# mainboard_3.net
KiCad netlist of a schematic drawn in EAGLE
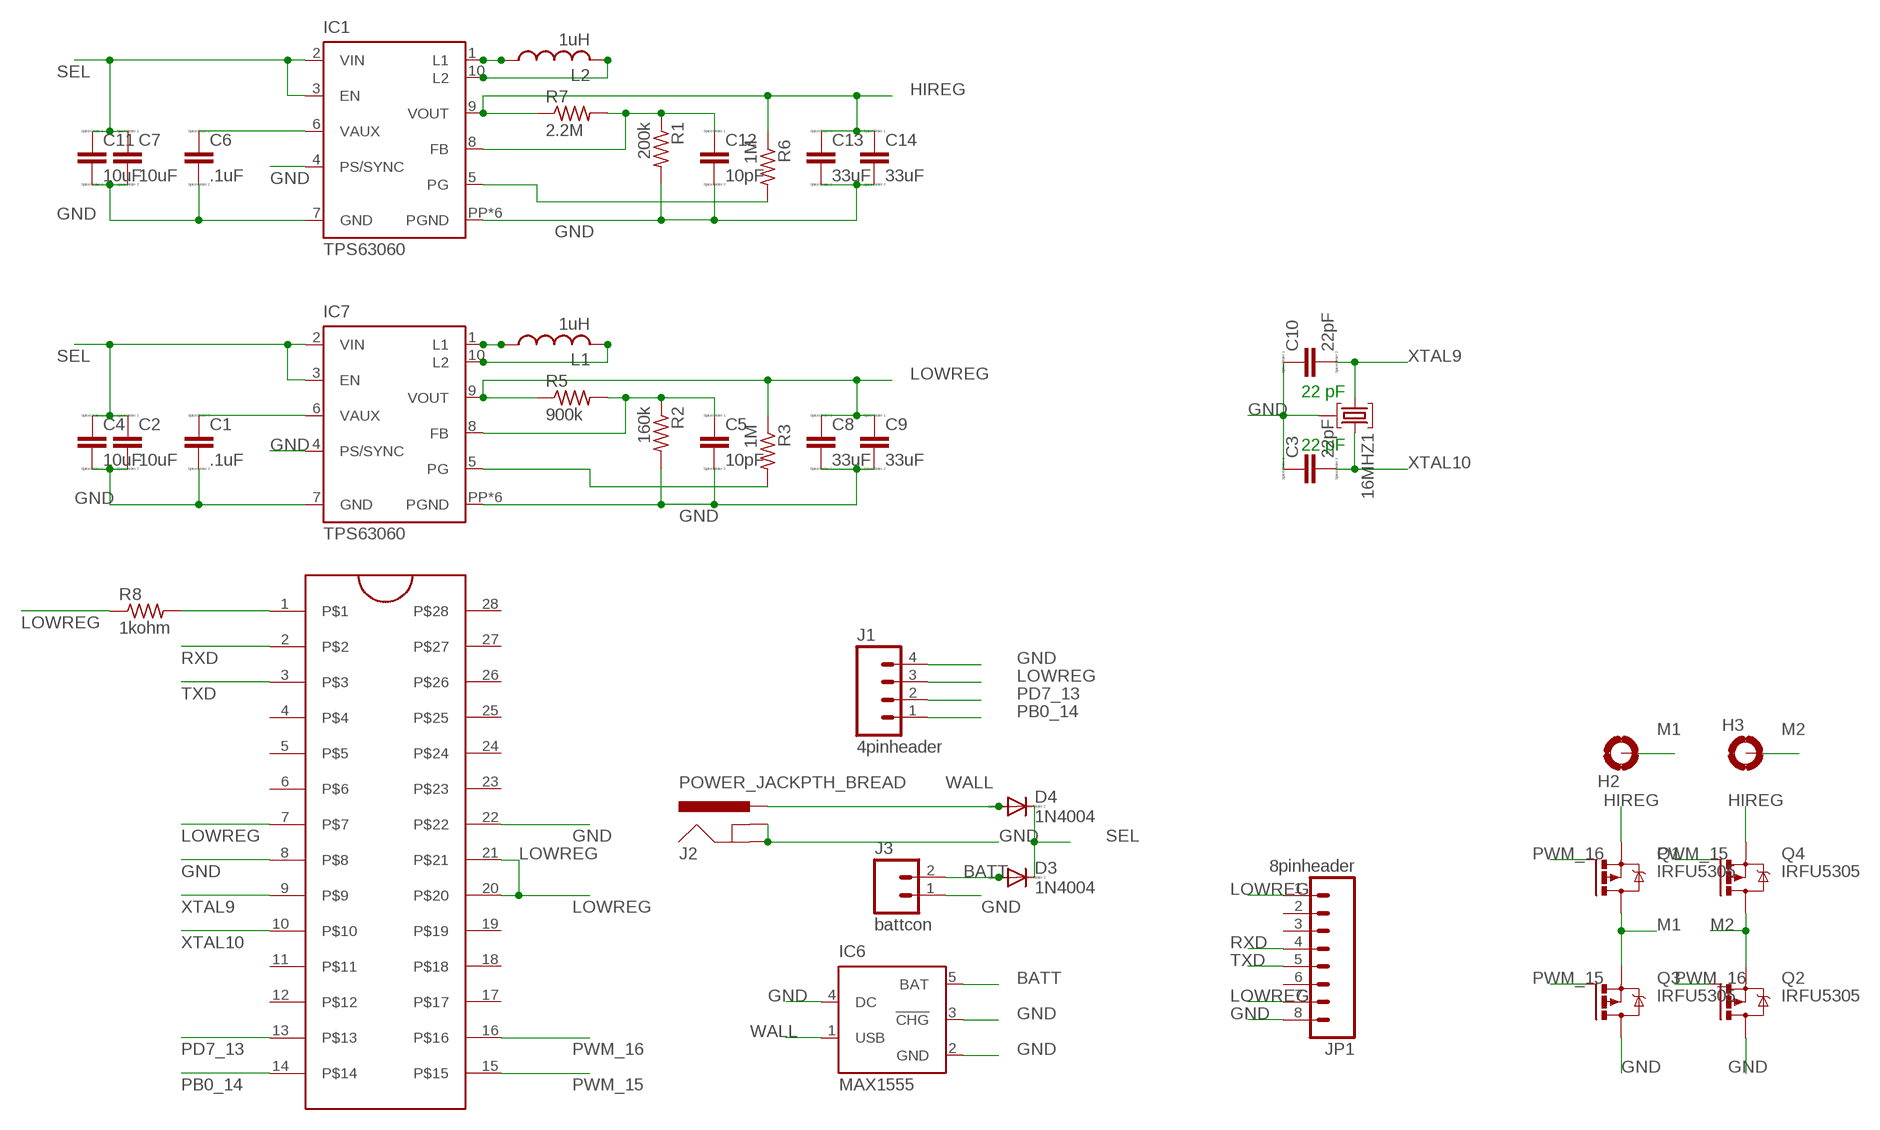
[diagram p0: schematic, sheet 1]

(export (version "E")
  (design (tool "Eeschema 10.0.6"))
  (components
    (comp (ref "16MHZ1")
      (value "HC49-HC49-3L")
      (footprint "eagle-import:HC49-3L")
      (libsource (lib "eagle-import") (part "HC49-HC49-3L"))
    )
    (comp (ref "C1")
      (value ".1uF")
      (footprint "eagle-import:C0805")
      (libsource (lib "eagle-import") (part "C"))
    )
    (comp (ref "C2")
      (value "10uF")
      (footprint "eagle-import:C3216")
      (libsource (lib "eagle-import") (part "CC3216"))
    )
    (comp (ref "C3")
      (value "22pF")
      (footprint "eagle-import:C0805")
      (libsource (lib "eagle-import") (part "C"))
    )
    (comp (ref "C4")
      (value "10uF")
      (footprint "eagle-import:C3216")
      (libsource (lib "eagle-import") (part "CC3216"))
    )
    (comp (ref "C5")
      (value "10pF")
      (footprint "eagle-import:C1206")
      (libsource (lib "eagle-import") (part "CC1206"))
    )
    (comp (ref "C6")
      (value ".1uF")
      (footprint "eagle-import:C0805")
      (libsource (lib "eagle-import") (part "C"))
    )
    (comp (ref "C7")
      (value "10uF")
      (footprint "eagle-import:C3216")
      (libsource (lib "eagle-import") (part "CC3216"))
    )
    (comp (ref "C8")
      (value "33uF")
      (footprint "eagle-import:C3216")
      (libsource (lib "eagle-import") (part "CC3216"))
    )
    (comp (ref "C9")
      (value "33uF")
      (footprint "eagle-import:C3216")
      (libsource (lib "eagle-import") (part "CC3216"))
    )
    (comp (ref "C10")
      (value "22pF")
      (footprint "eagle-import:C0805")
      (libsource (lib "eagle-import") (part "C"))
    )
    (comp (ref "C11")
      (value "10uF")
      (footprint "eagle-import:C3216")
      (libsource (lib "eagle-import") (part "CC3216"))
    )
    (comp (ref "C12")
      (value "10pF")
      (footprint "eagle-import:C1206")
      (libsource (lib "eagle-import") (part "CC1206"))
    )
    (comp (ref "C13")
      (value "33uF")
      (footprint "eagle-import:C3216")
      (libsource (lib "eagle-import") (part "CC3216"))
    )
    (comp (ref "C14")
      (value "33uF")
      (footprint "eagle-import:C3216")
      (libsource (lib "eagle-import") (part "CC3216"))
    )
    (comp (ref "D3")
      (value "1N4004")
      (footprint "eagle-import:DO41-10")
      (libsource (lib "eagle-import") (part "1N4004"))
    )
    (comp (ref "D4")
      (value "1N4004")
      (footprint "eagle-import:DO41-10")
      (libsource (lib "eagle-import") (part "1N4004"))
    )
    (comp (ref "H2")
      (value "MOUNT-PAD-ROUND4.1")
      (footprint "eagle-import:4,1-PAD")
      (libsource (lib "eagle-import") (part "MOUNT-PAD-ROUND4.1"))
    )
    (comp (ref "H3")
      (value "MOUNT-PAD-ROUND4.1")
      (footprint "eagle-import:4,1-PAD")
      (libsource (lib "eagle-import") (part "MOUNT-PAD-ROUND4.1"))
    )
    (comp (ref "IC1")
      (value "TPS63060")
      (footprint "eagle-import:DSC-S-PWSON-N10")
      (libsource (lib "eagle-import") (part "TPS63060"))
    )
    (comp (ref "IC6")
      (value "MAX1555")
      (footprint "eagle-import:SOT23-5L")
      (fields (field (name "MF") "MAXIM") (field (name "MPN") "MAX1555EZK+T"))
      (libsource (lib "eagle-import") (part "MAX1555"))
    )
    (comp (ref "IC7")
      (value "TPS63060")
      (footprint "eagle-import:DSC-S-PWSON-N10")
      (libsource (lib "eagle-import") (part "TPS63060"))
    )
    (comp (ref "J1")
      (value "4pinheader")
      (footprint "eagle-import:1X04_LONGPADS")
      (libsource (lib "eagle-import") (part "M04LONGPADS"))
    )
    (comp (ref "J2")
      (value "POWER_JACKPTH_BREAD")
      (footprint "eagle-import:POWER_JACK_PTH_BREAD")
      (libsource (lib "eagle-import") (part "POWER_JACKPTH_BREAD"))
    )
    (comp (ref "J3")
      (value "battcon")
      (footprint "eagle-import:JST-2-PTH-VERT")
      (libsource (lib "eagle-import") (part "M02JST-PTH-VERT"))
    )
    (comp (ref "JP1")
      (value "8pinheader")
      (footprint "eagle-import:1X08_LONGPADS")
      (libsource (lib "eagle-import") (part "M08LONGPADS"))
    )
    (comp (ref "L1")
      (value "1uH")
      (footprint "eagle-import:L4532P")
      (libsource (lib "eagle-import") (part "L-USL4532P"))
    )
    (comp (ref "L2")
      (value "1uH")
      (footprint "eagle-import:L4532P")
      (libsource (lib "eagle-import") (part "L-USL4532P"))
    )
    (comp (ref "Q1")
      (value "IRFU5305")
      (footprint "eagle-import:I-PAK_TO251AA")
      (libsource (lib "eagle-import") (part "IRF?5305U"))
    )
    (comp (ref "Q2")
      (value "IRFU5305")
      (footprint "eagle-import:I-PAK_TO251AA")
      (libsource (lib "eagle-import") (part "IRF?5305U"))
    )
    (comp (ref "Q3")
      (value "IRFU5305")
      (footprint "eagle-import:I-PAK_TO251AA")
      (libsource (lib "eagle-import") (part "IRF?5305U"))
    )
    (comp (ref "Q4")
      (value "IRFU5305")
      (footprint "eagle-import:I-PAK_TO251AA")
      (libsource (lib "eagle-import") (part "IRF?5305U"))
    )
    (comp (ref "R1")
      (value "200k")
      (footprint "eagle-import:M0805")
      (libsource (lib "eagle-import") (part "R-US_M0805"))
    )
    (comp (ref "R2")
      (value "160k")
      (footprint "eagle-import:M0805")
      (libsource (lib "eagle-import") (part "R-US_M0805"))
    )
    (comp (ref "R3")
      (value "1M")
      (footprint "eagle-import:M0805")
      (libsource (lib "eagle-import") (part "R-US_M0805"))
    )
    (comp (ref "R5")
      (value "900k")
      (footprint "eagle-import:M3216")
      (libsource (lib "eagle-import") (part "R-US_M3216"))
    )
    (comp (ref "R6")
      (value "1M")
      (footprint "eagle-import:M0805")
      (libsource (lib "eagle-import") (part "R-US_M0805"))
    )
    (comp (ref "R7")
      (value "2.2M")
      (footprint "eagle-import:M3216")
      (libsource (lib "eagle-import") (part "R-US_M3216"))
    )
    (comp (ref "R8")
      (value "1kohm")
      (footprint "eagle-import:M0805")
      (libsource (lib "eagle-import") (part "R-US_M0805"))
    )
    (comp (ref "U$1")
      (value "ZIFSOCKET-28-3ZIFFSOCKET-28-3")
      (footprint "eagle-import:DIL28-3-ZIF_SOCKET")
      (libsource (lib "eagle-import") (part "ZIFSOCKET-28-3ZIFFSOCKET-28-3"))
    )
  )
  (nets
    (net (code "1") (name "/BATT") (class "Default")
      (node (ref "D3") (pin "A") (pinfunction "A_A") (pintype "passive"))
      (node (ref "IC6") (pin "5") (pinfunction "BAT_5") (pintype "passive"))
      (node (ref "J3") (pin "2") (pinfunction "2_2") (pintype "passive"))
    )
    (net (code "2") (name "/GND") (class "Default")
      (node (ref "16MHZ1") (pin "2") (pinfunction "2_2") (pintype "passive"))
      (node (ref "C1") (pin "2") (pinfunction "2_2") (pintype "passive"))
      (node (ref "C10") (pin "1") (pinfunction "1_1") (pintype "passive"))
      (node (ref "C11") (pin "2") (pinfunction "2_2") (pintype "passive"))
      (node (ref "C12") (pin "2") (pinfunction "2_2") (pintype "passive"))
      (node (ref "C13") (pin "2") (pinfunction "2_2") (pintype "passive"))
      (node (ref "C14") (pin "2") (pinfunction "2_2") (pintype "passive"))
      (node (ref "C2") (pin "2") (pinfunction "2_2") (pintype "passive"))
      (node (ref "C3") (pin "1") (pinfunction "1_1") (pintype "passive"))
      (node (ref "C4") (pin "2") (pinfunction "2_2") (pintype "passive"))
      (node (ref "C5") (pin "2") (pinfunction "2_2") (pintype "passive"))
      (node (ref "C6") (pin "2") (pinfunction "2_2") (pintype "passive"))
      (node (ref "C7") (pin "2") (pinfunction "2_2") (pintype "passive"))
      (node (ref "C8") (pin "2") (pinfunction "2_2") (pintype "passive"))
      (node (ref "C9") (pin "2") (pinfunction "2_2") (pintype "passive"))
      (node (ref "IC1") (pin "4") (pinfunction "PS/SYNC_4") (pintype "input"))
      (node (ref "IC1") (pin "7") (pinfunction "GND_7") (pintype "input"))
      (node (ref "IC1") (pin "PP") (pinfunction "PGND_PP") (pintype "power_in"))
      (node (ref "IC1") (pin "PP@1") (pinfunction "PGND_PP@1") (pintype "power_in"))
      (node (ref "IC1") (pin "PP@2") (pinfunction "PGND_PP@2") (pintype "power_in"))
      (node (ref "IC1") (pin "PP@3") (pinfunction "PGND_PP@3") (pintype "power_in"))
      (node (ref "IC1") (pin "PP@4") (pinfunction "PGND_PP@4") (pintype "power_in"))
      (node (ref "IC1") (pin "PP@7") (pinfunction "PGND_PP@7") (pintype "power_in"))
      (node (ref "IC6") (pin "2") (pinfunction "GND_2") (pintype "power_in"))
      (node (ref "IC6") (pin "3") (pinfunction "~{CHG}_3") (pintype "output"))
      (node (ref "IC6") (pin "4") (pinfunction "DC_4") (pintype "input"))
      (node (ref "IC7") (pin "4") (pinfunction "PS/SYNC_4") (pintype "input"))
      (node (ref "IC7") (pin "7") (pinfunction "GND_7") (pintype "input"))
      (node (ref "IC7") (pin "PP") (pinfunction "PGND_PP") (pintype "power_in"))
      (node (ref "IC7") (pin "PP@1") (pinfunction "PGND_PP@1") (pintype "power_in"))
      (node (ref "IC7") (pin "PP@2") (pinfunction "PGND_PP@2") (pintype "power_in"))
      (node (ref "IC7") (pin "PP@3") (pinfunction "PGND_PP@3") (pintype "power_in"))
      (node (ref "IC7") (pin "PP@4") (pinfunction "PGND_PP@4") (pintype "power_in"))
      (node (ref "IC7") (pin "PP@7") (pinfunction "PGND_PP@7") (pintype "power_in"))
      (node (ref "J1") (pin "4") (pinfunction "4_4") (pintype "passive"))
      (node (ref "J2") (pin "GND") (pinfunction "GND_GND") (pintype "bidirectional"))
      (node (ref "J2") (pin "GNDBREAK") (pinfunction "GNDBREAK_GNDBREAK") (pintype "bidirectional"))
      (node (ref "J3") (pin "1") (pinfunction "1_1") (pintype "passive"))
      (node (ref "JP1") (pin "8") (pinfunction "8_8") (pintype "passive"))
      (node (ref "Q2") (pin "2") (pinfunction "D_2") (pintype "passive"))
      (node (ref "Q3") (pin "2") (pinfunction "D_2") (pintype "passive"))
      (node (ref "R1") (pin "2") (pinfunction "2_2") (pintype "passive"))
      (node (ref "R2") (pin "2") (pinfunction "2_2") (pintype "passive"))
      (node (ref "U$1") (pin "22") (pinfunction "P$22_22") (pintype "bidirectional"))
      (node (ref "U$1") (pin "8") (pinfunction "P$8_8") (pintype "bidirectional"))
    )
    (net (code "3") (name "/HIREG") (class "Default")
      (node (ref "C13") (pin "1") (pinfunction "1_1") (pintype "passive"))
      (node (ref "C14") (pin "1") (pinfunction "1_1") (pintype "passive"))
      (node (ref "IC1") (pin "9") (pinfunction "VOUT_9") (pintype "output"))
      (node (ref "Q1") (pin "3") (pinfunction "S_3") (pintype "passive"))
      (node (ref "Q4") (pin "3") (pinfunction "S_3") (pintype "passive"))
      (node (ref "R6") (pin "1") (pinfunction "1_1") (pintype "passive"))
      (node (ref "R7") (pin "1") (pinfunction "1_1") (pintype "passive"))
    )
    (net (code "4") (name "/LOWREG") (class "Default")
      (node (ref "C8") (pin "1") (pinfunction "1_1") (pintype "passive"))
      (node (ref "C9") (pin "1") (pinfunction "1_1") (pintype "passive"))
      (node (ref "IC7") (pin "9") (pinfunction "VOUT_9") (pintype "output"))
      (node (ref "J1") (pin "3") (pinfunction "3_3") (pintype "passive"))
      (node (ref "JP1") (pin "1") (pinfunction "1_1") (pintype "passive"))
      (node (ref "JP1") (pin "7") (pinfunction "7_7") (pintype "passive"))
      (node (ref "R3") (pin "1") (pinfunction "1_1") (pintype "passive"))
      (node (ref "R5") (pin "1") (pinfunction "1_1") (pintype "passive"))
      (node (ref "R8") (pin "1") (pinfunction "1_1") (pintype "passive"))
      (node (ref "U$1") (pin "20") (pinfunction "P$20_20") (pintype "bidirectional"))
      (node (ref "U$1") (pin "21") (pinfunction "P$21_21") (pintype "bidirectional"))
      (node (ref "U$1") (pin "7") (pinfunction "P$7_7") (pintype "bidirectional"))
    )
    (net (code "5") (name "/M1") (class "Default")
      (node (ref "H2") (pin "B4,1") (pinfunction "MOUNT_B4,1") (pintype "passive"))
      (node (ref "Q1") (pin "2") (pinfunction "D_2") (pintype "passive"))
      (node (ref "Q3") (pin "3") (pinfunction "S_3") (pintype "passive"))
    )
    (net (code "6") (name "/M2") (class "Default")
      (node (ref "H3") (pin "B4,1") (pinfunction "MOUNT_B4,1") (pintype "passive"))
      (node (ref "Q2") (pin "3") (pinfunction "S_3") (pintype "passive"))
      (node (ref "Q4") (pin "2") (pinfunction "D_2") (pintype "passive"))
    )
    (net (code "7") (name "/PB0_14") (class "Default")
      (node (ref "J1") (pin "1") (pinfunction "1_1") (pintype "passive"))
      (node (ref "U$1") (pin "14") (pinfunction "P$14_14") (pintype "bidirectional"))
    )
    (net (code "8") (name "/PD7_13") (class "Default")
      (node (ref "J1") (pin "2") (pinfunction "2_2") (pintype "passive"))
      (node (ref "U$1") (pin "13") (pinfunction "P$13_13") (pintype "bidirectional"))
    )
    (net (code "9") (name "/PWM_15") (class "Default")
      (node (ref "Q3") (pin "1") (pinfunction "G_1") (pintype "passive"))
      (node (ref "Q4") (pin "1") (pinfunction "G_1") (pintype "passive"))
      (node (ref "U$1") (pin "15") (pinfunction "P$15_15") (pintype "bidirectional"))
    )
    (net (code "10") (name "/PWM_16") (class "Default")
      (node (ref "Q1") (pin "1") (pinfunction "G_1") (pintype "passive"))
      (node (ref "Q2") (pin "1") (pinfunction "G_1") (pintype "passive"))
      (node (ref "U$1") (pin "16") (pinfunction "P$16_16") (pintype "bidirectional"))
    )
    (net (code "11") (name "/RXD") (class "Default")
      (node (ref "JP1") (pin "4") (pinfunction "4_4") (pintype "passive"))
      (node (ref "U$1") (pin "2") (pinfunction "P$2_2") (pintype "bidirectional"))
    )
    (net (code "12") (name "/SEL") (class "Default")
      (node (ref "C11") (pin "1") (pinfunction "1_1") (pintype "passive"))
      (node (ref "C2") (pin "1") (pinfunction "1_1") (pintype "passive"))
      (node (ref "C4") (pin "1") (pinfunction "1_1") (pintype "passive"))
      (node (ref "C7") (pin "1") (pinfunction "1_1") (pintype "passive"))
      (node (ref "D3") (pin "C") (pinfunction "C_C") (pintype "passive"))
      (node (ref "D4") (pin "C") (pinfunction "C_C") (pintype "passive"))
      (node (ref "IC1") (pin "2") (pinfunction "VIN_2") (pintype "input"))
      (node (ref "IC1") (pin "3") (pinfunction "EN_3") (pintype "input"))
      (node (ref "IC7") (pin "2") (pinfunction "VIN_2") (pintype "input"))
      (node (ref "IC7") (pin "3") (pinfunction "EN_3") (pintype "input"))
    )
    (net (code "13") (name "/TXD") (class "Default")
      (node (ref "JP1") (pin "5") (pinfunction "5_5") (pintype "passive"))
      (node (ref "U$1") (pin "3") (pinfunction "P$3_3") (pintype "bidirectional"))
    )
    (net (code "14") (name "/WALL") (class "Default")
      (node (ref "D4") (pin "A") (pinfunction "A_A") (pintype "passive"))
      (node (ref "IC6") (pin "1") (pinfunction "USB_1") (pintype "input"))
      (node (ref "J2") (pin "PWR") (pinfunction "PWR_PWR") (pintype "bidirectional"))
    )
    (net (code "15") (name "/XTAL9") (class "Default")
      (node (ref "16MHZ1") (pin "1") (pinfunction "1_1") (pintype "passive"))
      (node (ref "C10") (pin "2") (pinfunction "2_2") (pintype "passive"))
      (node (ref "U$1") (pin "9") (pinfunction "P$9_9") (pintype "bidirectional"))
    )
    (net (code "16") (name "/XTAL10") (class "Default")
      (node (ref "16MHZ1") (pin "3") (pinfunction "3_3") (pintype "passive"))
      (node (ref "C3") (pin "2") (pinfunction "2_2") (pintype "passive"))
      (node (ref "U$1") (pin "10") (pinfunction "P$10_10") (pintype "bidirectional"))
    )
    (net (code "17") (name "Net-(IC1-FB)") (class "Default")
      (node (ref "C12") (pin "1") (pinfunction "1_1") (pintype "passive"))
      (node (ref "IC1") (pin "8") (pinfunction "FB_8") (pintype "input"))
      (node (ref "R1") (pin "1") (pinfunction "1_1") (pintype "passive"))
      (node (ref "R7") (pin "2") (pinfunction "2_2") (pintype "passive"))
    )
    (net (code "18") (name "Net-(IC1-L1)") (class "Default")
      (node (ref "IC1") (pin "1") (pinfunction "L1_1") (pintype "input"))
      (node (ref "L2") (pin "1") (pinfunction "1_1") (pintype "passive"))
    )
    (net (code "19") (name "Net-(IC1-L2)") (class "Default")
      (node (ref "IC1") (pin "10") (pinfunction "L2_10") (pintype "input"))
      (node (ref "L2") (pin "2") (pinfunction "2_2") (pintype "passive"))
    )
    (net (code "20") (name "Net-(IC1-PG)") (class "Default")
      (node (ref "IC1") (pin "5") (pinfunction "PG_5") (pintype "output"))
      (node (ref "R6") (pin "2") (pinfunction "2_2") (pintype "passive"))
    )
    (net (code "21") (name "Net-(IC1-VAUX)") (class "Default")
      (node (ref "C6") (pin "1") (pinfunction "1_1") (pintype "passive"))
      (node (ref "IC1") (pin "6") (pinfunction "VAUX_6") (pintype "power_in"))
    )
    (net (code "22") (name "Net-(IC7-FB)") (class "Default")
      (node (ref "C5") (pin "1") (pinfunction "1_1") (pintype "passive"))
      (node (ref "IC7") (pin "8") (pinfunction "FB_8") (pintype "input"))
      (node (ref "R2") (pin "1") (pinfunction "1_1") (pintype "passive"))
      (node (ref "R5") (pin "2") (pinfunction "2_2") (pintype "passive"))
    )
    (net (code "23") (name "Net-(IC7-L1)") (class "Default")
      (node (ref "IC7") (pin "1") (pinfunction "L1_1") (pintype "input"))
      (node (ref "L1") (pin "1") (pinfunction "1_1") (pintype "passive"))
    )
    (net (code "24") (name "Net-(IC7-L2)") (class "Default")
      (node (ref "IC7") (pin "10") (pinfunction "L2_10") (pintype "input"))
      (node (ref "L1") (pin "2") (pinfunction "2_2") (pintype "passive"))
    )
    (net (code "25") (name "Net-(IC7-PG)") (class "Default")
      (node (ref "IC7") (pin "5") (pinfunction "PG_5") (pintype "output"))
      (node (ref "R3") (pin "2") (pinfunction "2_2") (pintype "passive"))
    )
    (net (code "26") (name "Net-(IC7-VAUX)") (class "Default")
      (node (ref "C1") (pin "1") (pinfunction "1_1") (pintype "passive"))
      (node (ref "IC7") (pin "6") (pinfunction "VAUX_6") (pintype "power_in"))
    )
    (net (code "27") (name "Net-(U$1-P$1)") (class "Default")
      (node (ref "R8") (pin "2") (pinfunction "2_2") (pintype "passive"))
      (node (ref "U$1") (pin "1") (pinfunction "P$1_1") (pintype "bidirectional"))
    )
    (net (code "28") (name "unconnected-(JP1-Pad2)") (class "Default")
      (node (ref "JP1") (pin "2") (pinfunction "2_2") (pintype "passive"))
    )
    (net (code "29") (name "unconnected-(JP1-Pad3)") (class "Default")
      (node (ref "JP1") (pin "3") (pinfunction "3_3") (pintype "passive"))
    )
    (net (code "30") (name "unconnected-(JP1-Pad6)") (class "Default")
      (node (ref "JP1") (pin "6") (pinfunction "6_6") (pintype "passive"))
    )
    (net (code "31") (name "unconnected-(U$1-P$4-Pad4)") (class "Default")
      (node (ref "U$1") (pin "4") (pinfunction "P$4_4") (pintype "bidirectional"))
    )
    (net (code "32") (name "unconnected-(U$1-P$5-Pad5)") (class "Default")
      (node (ref "U$1") (pin "5") (pinfunction "P$5_5") (pintype "bidirectional"))
    )
    (net (code "33") (name "unconnected-(U$1-P$6-Pad6)") (class "Default")
      (node (ref "U$1") (pin "6") (pinfunction "P$6_6") (pintype "bidirectional"))
    )
    (net (code "34") (name "unconnected-(U$1-P$11-Pad11)") (class "Default")
      (node (ref "U$1") (pin "11") (pinfunction "P$11_11") (pintype "bidirectional"))
    )
    (net (code "35") (name "unconnected-(U$1-P$12-Pad12)") (class "Default")
      (node (ref "U$1") (pin "12") (pinfunction "P$12_12") (pintype "bidirectional"))
    )
    (net (code "36") (name "unconnected-(U$1-P$17-Pad17)") (class "Default")
      (node (ref "U$1") (pin "17") (pinfunction "P$17_17") (pintype "bidirectional"))
    )
    (net (code "37") (name "unconnected-(U$1-P$18-Pad18)") (class "Default")
      (node (ref "U$1") (pin "18") (pinfunction "P$18_18") (pintype "bidirectional"))
    )
    (net (code "38") (name "unconnected-(U$1-P$19-Pad19)") (class "Default")
      (node (ref "U$1") (pin "19") (pinfunction "P$19_19") (pintype "bidirectional"))
    )
    (net (code "39") (name "unconnected-(U$1-P$23-Pad23)") (class "Default")
      (node (ref "U$1") (pin "23") (pinfunction "P$23_23") (pintype "bidirectional"))
    )
    (net (code "40") (name "unconnected-(U$1-P$24-Pad24)") (class "Default")
      (node (ref "U$1") (pin "24") (pinfunction "P$24_24") (pintype "bidirectional"))
    )
    (net (code "41") (name "unconnected-(U$1-P$25-Pad25)") (class "Default")
      (node (ref "U$1") (pin "25") (pinfunction "P$25_25") (pintype "bidirectional"))
    )
    (net (code "42") (name "unconnected-(U$1-P$26-Pad26)") (class "Default")
      (node (ref "U$1") (pin "26") (pinfunction "P$26_26") (pintype "bidirectional"))
    )
    (net (code "43") (name "unconnected-(U$1-P$27-Pad27)") (class "Default")
      (node (ref "U$1") (pin "27") (pinfunction "P$27_27") (pintype "bidirectional"))
    )
    (net (code "44") (name "unconnected-(U$1-P$28-Pad28)") (class "Default")
      (node (ref "U$1") (pin "28") (pinfunction "P$28_28") (pintype "bidirectional"))
    )
  )
)
